# board.net
KiCad netlist of a schematic drawn in EAGLE
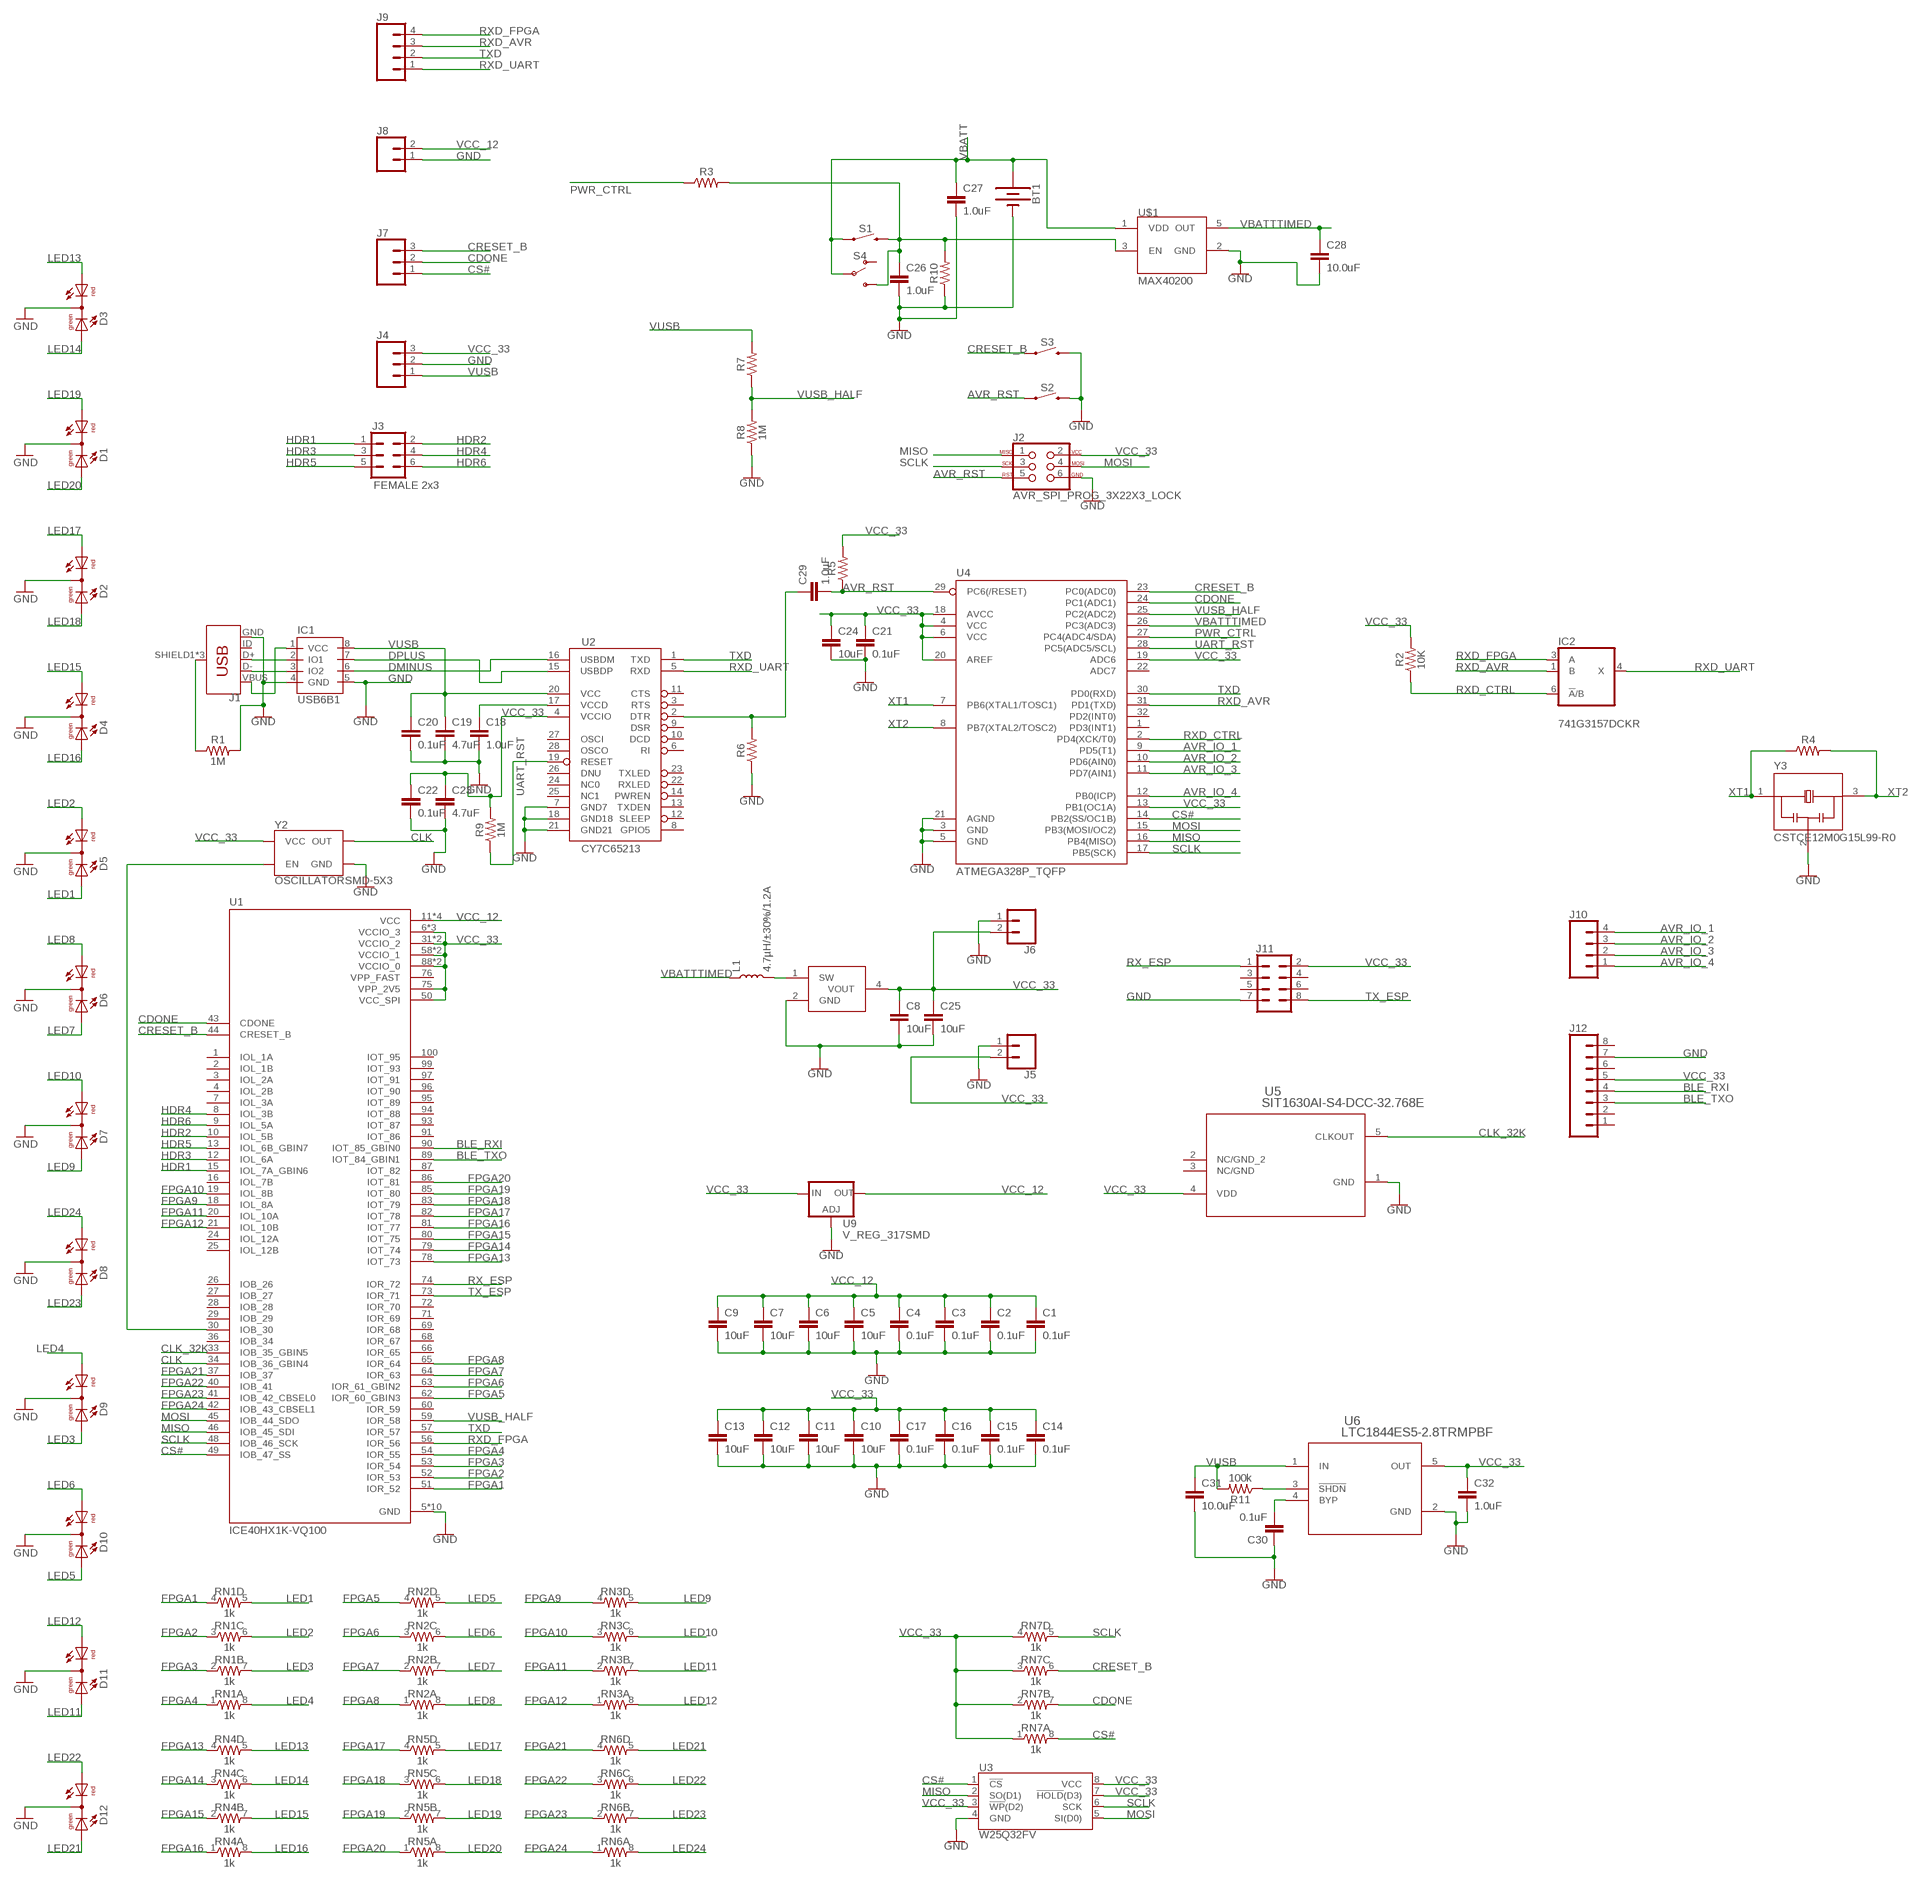
[diagram p0: schematic, sheet 1]

(export (version "E")
  (design (tool "Eeschema 10.0.6"))
  (components
    (comp (ref "BT1")
      (value "BATTERY-20MM_SMD")
      (footprint "eagle-import:BATTCON_20MM")
      (libsource (lib "eagle-import") (part "BATTERY-20MM_SMD"))
    )
    (comp (ref "C1")
      (value "0.1uF")
      (footprint "eagle-import:0805")
      (libsource (lib "eagle-import") (part "1.0UF-0805-25V-10%"))
    )
    (comp (ref "C2")
      (value "0.1uF")
      (footprint "eagle-import:0805")
      (libsource (lib "eagle-import") (part "1.0UF-0805-25V-10%"))
    )
    (comp (ref "C3")
      (value "0.1uF")
      (footprint "eagle-import:0805")
      (libsource (lib "eagle-import") (part "1.0UF-0805-25V-10%"))
    )
    (comp (ref "C4")
      (value "0.1uF")
      (footprint "eagle-import:0805")
      (libsource (lib "eagle-import") (part "1.0UF-0805-25V-10%"))
    )
    (comp (ref "C5")
      (value "10uF")
      (footprint "eagle-import:0805")
      (libsource (lib "eagle-import") (part "10UF-0805-10V-10%"))
    )
    (comp (ref "C6")
      (value "10uF")
      (footprint "eagle-import:0805")
      (libsource (lib "eagle-import") (part "10UF-0805-10V-10%"))
    )
    (comp (ref "C7")
      (value "10uF")
      (footprint "eagle-import:0805")
      (libsource (lib "eagle-import") (part "10UF-0805-10V-10%"))
    )
    (comp (ref "C8")
      (value "10uF")
      (footprint "eagle-import:0805")
      (libsource (lib "eagle-import") (part "22UF-0805-6.3V-20%"))
    )
    (comp (ref "C9")
      (value "10uF")
      (footprint "eagle-import:0805")
      (libsource (lib "eagle-import") (part "10UF-0805-10V-10%"))
    )
    (comp (ref "C10")
      (value "10uF")
      (footprint "eagle-import:0805")
      (libsource (lib "eagle-import") (part "10UF-0805-10V-10%"))
    )
    (comp (ref "C11")
      (value "10uF")
      (footprint "eagle-import:0805")
      (libsource (lib "eagle-import") (part "10UF-0805-10V-10%"))
    )
    (comp (ref "C12")
      (value "10uF")
      (footprint "eagle-import:0805")
      (libsource (lib "eagle-import") (part "10UF-0805-10V-10%"))
    )
    (comp (ref "C13")
      (value "10uF")
      (footprint "eagle-import:0805")
      (libsource (lib "eagle-import") (part "10UF-0805-10V-10%"))
    )
    (comp (ref "C14")
      (value "0.1uF")
      (footprint "eagle-import:0805")
      (libsource (lib "eagle-import") (part "1.0UF-0805-25V-(+80/-20%)"))
    )
    (comp (ref "C15")
      (value "0.1uF")
      (footprint "eagle-import:0805")
      (libsource (lib "eagle-import") (part "1.0UF-0805-25V-(+80/-20%)"))
    )
    (comp (ref "C16")
      (value "0.1uF")
      (footprint "eagle-import:0805")
      (libsource (lib "eagle-import") (part "1.0UF-0805-25V-(+80/-20%)"))
    )
    (comp (ref "C17")
      (value "0.1uF")
      (footprint "eagle-import:0805")
      (libsource (lib "eagle-import") (part "1.0UF-0805-25V-(+80/-20%)"))
    )
    (comp (ref "C18")
      (value "1.0uF")
      (footprint "eagle-import:0805")
      (libsource (lib "eagle-import") (part "1.0UF-0805-25V-10%"))
    )
    (comp (ref "C19")
      (value "4.7uF")
      (footprint "eagle-import:0805")
      (libsource (lib "eagle-import") (part "10UF-0805-10V-10%"))
    )
    (comp (ref "C20")
      (value "0.1uF")
      (footprint "eagle-import:0805")
      (libsource (lib "eagle-import") (part "1.0UF-0805-25V-10%"))
    )
    (comp (ref "C21")
      (value "0.1uF")
      (footprint "eagle-import:0805")
      (libsource (lib "eagle-import") (part "1.0UF-0805-25V-10%"))
    )
    (comp (ref "C22")
      (value "0.1uF")
      (footprint "eagle-import:0805")
      (libsource (lib "eagle-import") (part "1.0UF-0805-25V-10%"))
    )
    (comp (ref "C23")
      (value "4.7uF")
      (footprint "eagle-import:0805")
      (libsource (lib "eagle-import") (part "1.0UF-0805-25V-10%"))
    )
    (comp (ref "C24")
      (value "10uF")
      (footprint "eagle-import:0805")
      (libsource (lib "eagle-import") (part "1.0UF-0805-25V-10%"))
    )
    (comp (ref "C25")
      (value "10uF")
      (footprint "eagle-import:0805")
      (libsource (lib "eagle-import") (part "1.0UF-0805-25V-10%"))
    )
    (comp (ref "C26")
      (value "1.0uF")
      (footprint "eagle-import:0603")
      (libsource (lib "eagle-import") (part "1.0UF-0603-16V-10%"))
    )
    (comp (ref "C27")
      (value "1.0uF")
      (footprint "eagle-import:0603")
      (libsource (lib "eagle-import") (part "1.0UF-0603-16V-10%"))
    )
    (comp (ref "C28")
      (value "10.0uF")
      (footprint "eagle-import:0603")
      (libsource (lib "eagle-import") (part "1.0UF-0603-16V-10%"))
    )
    (comp (ref "C29")
      (value "1.0uF")
      (footprint "eagle-import:0805")
      (libsource (lib "eagle-import") (part "1.0UF-0805-25V-(+80/-20%)"))
    )
    (comp (ref "C30")
      (value "0.1uF")
      (footprint "eagle-import:0805")
      (libsource (lib "eagle-import") (part "1.0UF-0805-25V-(+80/-20%)"))
    )
    (comp (ref "C31")
      (value "10.0uF")
      (footprint "eagle-import:0805")
      (libsource (lib "eagle-import") (part "1.0UF-0805-25V-(+80/-20%)"))
    )
    (comp (ref "C32")
      (value "1.0uF")
      (footprint "eagle-import:0805")
      (libsource (lib "eagle-import") (part "1.0UF-0805-25V-(+80/-20%)"))
    )
    (comp (ref "D1")
      (value "DUOLED5MM")
      (footprint "eagle-import:DUOLED5MM")
      (libsource (lib "eagle-import") (part "DUOLED5MM"))
    )
    (comp (ref "D2")
      (value "DUOLED5MM")
      (footprint "eagle-import:DUOLED5MM")
      (libsource (lib "eagle-import") (part "DUOLED5MM"))
    )
    (comp (ref "D3")
      (value "DUOLED5MM")
      (footprint "eagle-import:DUOLED5MM")
      (libsource (lib "eagle-import") (part "DUOLED5MM"))
    )
    (comp (ref "D4")
      (value "DUOLED5MM")
      (footprint "eagle-import:DUOLED5MM")
      (libsource (lib "eagle-import") (part "DUOLED5MM"))
    )
    (comp (ref "D5")
      (value "DUOLED5MM")
      (footprint "eagle-import:DUOLED5MM")
      (libsource (lib "eagle-import") (part "DUOLED5MM"))
    )
    (comp (ref "D6")
      (value "DUOLED5MM")
      (footprint "eagle-import:DUOLED5MM")
      (libsource (lib "eagle-import") (part "DUOLED5MM"))
    )
    (comp (ref "D7")
      (value "DUOLED5MM")
      (footprint "eagle-import:DUOLED5MM")
      (libsource (lib "eagle-import") (part "DUOLED5MM"))
    )
    (comp (ref "D8")
      (value "DUOLED5MM")
      (footprint "eagle-import:DUOLED5MM")
      (libsource (lib "eagle-import") (part "DUOLED5MM"))
    )
    (comp (ref "D9")
      (value "DUOLED5MM")
      (footprint "eagle-import:DUOLED5MM")
      (libsource (lib "eagle-import") (part "DUOLED5MM"))
    )
    (comp (ref "D10")
      (value "DUOLED5MM")
      (footprint "eagle-import:DUOLED5MM")
      (libsource (lib "eagle-import") (part "DUOLED5MM"))
    )
    (comp (ref "D11")
      (value "DUOLED5MM")
      (footprint "eagle-import:DUOLED5MM")
      (libsource (lib "eagle-import") (part "DUOLED5MM"))
    )
    (comp (ref "D12")
      (value "DUOLED5MM")
      (footprint "eagle-import:DUOLED5MM")
      (libsource (lib "eagle-import") (part "DUOLED5MM"))
    )
    (comp (ref "IC1")
      (value "USB6B1")
      (footprint "eagle-import:SO08")
      (libsource (lib "eagle-import") (part "USB6B1"))
    )
    (comp (ref "IC2")
      (value "741G3157DCKR")
      (footprint "eagle-import:DCK_R-PDSO-G6")
      (libsource (lib "eagle-import") (part "741G3157DCKR"))
    )
    (comp (ref "J1")
      (value "USB_MICRO-B_FEMALE-SMT")
      (footprint "eagle-import:USB-B-MICRO-SMD")
      (libsource (lib "eagle-import") (part "USB_MICRO-B_FEMALE-SMT"))
    )
    (comp (ref "J2")
      (value "AVR_SPI_PROG_3X22X3_LOCK")
      (footprint "eagle-import:2X3_LOCK")
      (libsource (lib "eagle-import") (part "AVR_SPI_PROG_3X22X3_LOCK"))
    )
    (comp (ref "J3")
      (value "FEMALE 2x3")
      (footprint "eagle-import:2X3")
      (libsource (lib "eagle-import") (part "CONN_03X2FEMALE"))
    )
    (comp (ref "J4")
      (value "CONN_03LOCK")
      (footprint "eagle-import:1X03_LOCK")
      (libsource (lib "eagle-import") (part "CONN_03LOCK"))
    )
    (comp (ref "J5")
      (value "CONN_02LOCK")
      (footprint "eagle-import:1X02_LOCK")
      (libsource (lib "eagle-import") (part "CONN_02LOCK"))
    )
    (comp (ref "J6")
      (value "CONN_02LOCK")
      (footprint "eagle-import:1X02_LOCK")
      (libsource (lib "eagle-import") (part "CONN_02LOCK"))
    )
    (comp (ref "J7")
      (value "CONN_03LOCK")
      (footprint "eagle-import:1X03_LOCK")
      (libsource (lib "eagle-import") (part "CONN_03LOCK"))
    )
    (comp (ref "J8")
      (value "CONN_02LOCK")
      (footprint "eagle-import:1X02_LOCK")
      (libsource (lib "eagle-import") (part "CONN_02LOCK"))
    )
    (comp (ref "J9")
      (value "CONN_04LOCK")
      (footprint "eagle-import:1X04_LOCK")
      (libsource (lib "eagle-import") (part "CONN_04LOCK"))
    )
    (comp (ref "J10")
      (value "CONN_04LOCK")
      (footprint "eagle-import:1X04_LOCK")
      (libsource (lib "eagle-import") (part "CONN_04LOCK"))
    )
    (comp (ref "J11")
      (value "CONN_04X2")
      (footprint "eagle-import:2X4")
      (libsource (lib "eagle-import") (part "CONN_04X2"))
    )
    (comp (ref "J12")
      (value "CONN_08LOCK")
      (footprint "eagle-import:1X08_LOCK")
      (libsource (lib "eagle-import") (part "CONN_08LOCK"))
    )
    (comp (ref "L1")
      (value "4.7µH/±30%/1.2A")
      (footprint "eagle-import:INDUCTOR_4.7UH")
      (libsource (lib "eagle-import") (part "INDUCTOR-CDRH-4.7UH"))
    )
    (comp (ref "R1")
      (value "1M")
      (footprint "eagle-import:0805")
      (libsource (lib "eagle-import") (part "RESISTOR0805"))
    )
    (comp (ref "R2")
      (value "10K")
      (footprint "eagle-import:0805")
      (libsource (lib "eagle-import") (part "RESISTOR0805"))
    )
    (comp (ref "R3")
      (value "RESISTOR0805")
      (footprint "eagle-import:0805")
      (libsource (lib "eagle-import") (part "RESISTOR0805"))
    )
    (comp (ref "R4")
      (value "RESISTOR0805")
      (footprint "eagle-import:0805")
      (libsource (lib "eagle-import") (part "RESISTOR0805"))
    )
    (comp (ref "R5")
      (value "RESISTOR0805")
      (footprint "eagle-import:0805")
      (libsource (lib "eagle-import") (part "RESISTOR0805"))
    )
    (comp (ref "R6")
      (value "RESISTOR0805")
      (footprint "eagle-import:0805")
      (libsource (lib "eagle-import") (part "RESISTOR0805"))
    )
    (comp (ref "R7")
      (value "RESISTOR0805")
      (footprint "eagle-import:0805")
      (libsource (lib "eagle-import") (part "RESISTOR0805"))
    )
    (comp (ref "R8")
      (value "1M")
      (footprint "eagle-import:0805")
      (libsource (lib "eagle-import") (part "RESISTOR0805"))
    )
    (comp (ref "R9")
      (value "1M")
      (footprint "eagle-import:0805")
      (libsource (lib "eagle-import") (part "RESISTOR0805"))
    )
    (comp (ref "R10")
      (value "RESISTOR0805")
      (footprint "eagle-import:0805")
      (libsource (lib "eagle-import") (part "RESISTOR0805"))
    )
    (comp (ref "R11")
      (value "100k")
      (footprint "eagle-import:0805")
      (libsource (lib "eagle-import") (part "RESISTOR0805"))
    )
    (comp (ref "RN1")
      (value "1k")
      (footprint "eagle-import:0805-ARV")
      (libsource (lib "eagle-import") (part "1KOHM-ARRAY(4)-0805_ARV-1/10W-5%"))
    )
    (comp (ref "RN2")
      (value "1k")
      (footprint "eagle-import:0805-ARV")
      (libsource (lib "eagle-import") (part "1KOHM-ARRAY(4)-0805_ARV-1/10W-5%"))
    )
    (comp (ref "RN3")
      (value "1k")
      (footprint "eagle-import:0805-ARV")
      (libsource (lib "eagle-import") (part "1KOHM-ARRAY(4)-0805_ARV-1/10W-5%"))
    )
    (comp (ref "RN4")
      (value "1k")
      (footprint "eagle-import:0805-ARV")
      (libsource (lib "eagle-import") (part "1KOHM-ARRAY(4)-0805_ARV-1/10W-5%"))
    )
    (comp (ref "RN5")
      (value "1k")
      (footprint "eagle-import:0805-ARV")
      (libsource (lib "eagle-import") (part "1KOHM-ARRAY(4)-0805_ARV-1/10W-5%"))
    )
    (comp (ref "RN6")
      (value "1k")
      (footprint "eagle-import:0805-ARV")
      (libsource (lib "eagle-import") (part "1KOHM-ARRAY(4)-0805_ARV-1/10W-5%"))
    )
    (comp (ref "RN7")
      (value "1k")
      (footprint "eagle-import:0805-ARV")
      (libsource (lib "eagle-import") (part "1KOHM-ARRAY(4)-0805_ARV-1/10W-5%"))
    )
    (comp (ref "S1")
      (value "MOMENTARY-SWITCH-SPST-SMD-5.2MM")
      (footprint "eagle-import:TACTILE_SWITCH_SMD_5.2MM")
      (libsource (lib "eagle-import") (part "MOMENTARY-SWITCH-SPST-SMD-5.2MM"))
    )
    (comp (ref "S2")
      (value "MOMENTARY-SWITCH-SPST-SMD-5.2MM")
      (footprint "eagle-import:TACTILE_SWITCH_SMD_5.2MM")
      (libsource (lib "eagle-import") (part "MOMENTARY-SWITCH-SPST-SMD-5.2MM"))
    )
    (comp (ref "S3")
      (value "MOMENTARY-SWITCH-SPST-SMD-5.2MM")
      (footprint "eagle-import:TACTILE_SWITCH_SMD_5.2MM")
      (libsource (lib "eagle-import") (part "MOMENTARY-SWITCH-SPST-SMD-5.2MM"))
    )
    (comp (ref "S4")
      (value "SWITCH-SPDT-PTH-11.6X4.0MM")
      (footprint "eagle-import:SWITCH_SPDT_PTH_11.6X4.0MM")
      (libsource (lib "eagle-import") (part "SWITCH-SPDT-PTH-11.6X4.0MM"))
    )
    (comp (ref "U$1")
      (value "MAX40200")
      (footprint "eagle-import:SOT95P280X145-5N")
      (libsource (lib "eagle-import") (part "MAX40200"))
    )
    (comp (ref "U$2")
      (value "TPS613221A")
      (footprint "eagle-import:SOT95P280X145-5N")
      (libsource (lib "eagle-import") (part "TPS613221A"))
    )
    (comp (ref "U1")
      (value "ICE40HX1K-VQ100")
      (footprint "eagle-import:QFP50P1600X1600X120-100N")
      (fields (field (name "MF") "Lattice Semiconductor"))
      (libsource (lib "eagle-import") (part "ICE40HX1K-VQ100"))
    )
    (comp (ref "U2")
      (value "CY7C65213")
      (footprint "eagle-import:SSOP28DB")
      (libsource (lib "eagle-import") (part "CY7C65213"))
    )
    (comp (ref "U3")
      (value "W25Q32FV")
      (footprint "eagle-import:SOIC-8")
      (libsource (lib "eagle-import") (part "W25Q32FVSS"))
    )
    (comp (ref "U4")
      (value "ATMEGA328P_TQFP")
      (footprint "eagle-import:TQFP32-08")
      (libsource (lib "eagle-import") (part "ATMEGA328P_TQFP"))
    )
    (comp (ref "U5")
      (value "SIT1630AI-S4-DCC-32.768E")
      (footprint "eagle-import:SOT_SIT1630-S_SIT")
      (fields (field (name "COPYRIGHT") "Copyright (C) 2018 Accelerated Designs. All rights reserved"))
      (libsource (lib "eagle-import") (part "SIT1630AI-S4-DCC-32.768E"))
    )
    (comp (ref "U6")
      (value "LTC1844ES5-2.8TRMPBF")
      (footprint "eagle-import:S_5_ADI")
      (fields
        (field (name "MANUFACTURER_PART_NUMBER") "LTC1844ES5-2.8#TRMPBF")
        (field (name "COPYRIGHT") "Copyright (C) 2016 Accelerated Designs. All rights reserved")
      )
      (libsource (lib "eagle-import") (part "LTC1844ES5-2.8TRMPBF"))
    )
    (comp (ref "U9")
      (value "V_REG_317SMD")
      (footprint "eagle-import:SOT223")
      (libsource (lib "eagle-import") (part "V_REG_317SMD"))
    )
    (comp (ref "Y2")
      (value "OSCILLATORSMD-5X3")
      (footprint "eagle-import:OSCILLATOR-SMD-5X3.2")
      (libsource (lib "eagle-import") (part "OSCILLATORSMD-5X3"))
    )
    (comp (ref "Y3")
      (value "CSTCE12M0G15L99-R0")
      (footprint "eagle-import:OSC_CSTCE12M0G15L99-R0")
      (fields (field (name "MF") "Murata Electronics"))
      (libsource (lib "eagle-import") (part "CSTCE12M0G15L99-R0"))
    )
  )
  (nets
    (net (code "1") (name "/AVR_IO_1") (class "Default")
      (node (ref "J10") (pin "4") (pinfunction "4_4") (pintype "passive"))
      (node (ref "U4") (pin "9") (pinfunction "PD5(T1)_9") (pintype "bidirectional"))
    )
    (net (code "2") (name "/AVR_IO_2") (class "Default")
      (node (ref "J10") (pin "3") (pinfunction "3_3") (pintype "passive"))
      (node (ref "U4") (pin "10") (pinfunction "PD6(AIN0)_10") (pintype "bidirectional"))
    )
    (net (code "3") (name "/AVR_IO_3") (class "Default")
      (node (ref "J10") (pin "2") (pinfunction "2_2") (pintype "passive"))
      (node (ref "U4") (pin "11") (pinfunction "PD7(AIN1)_11") (pintype "bidirectional"))
    )
    (net (code "4") (name "/AVR_IO_4") (class "Default")
      (node (ref "J10") (pin "1") (pinfunction "1_1") (pintype "passive"))
      (node (ref "U4") (pin "12") (pinfunction "PB0(ICP)_12") (pintype "bidirectional"))
    )
    (net (code "5") (name "/AVR_RST") (class "Default")
      (node (ref "C29") (pin "2") (pinfunction "2_2") (pintype "passive"))
      (node (ref "J2") (pin "5") (pinfunction "5_5") (pintype "passive"))
      (node (ref "R5") (pin "1") (pinfunction "1_1") (pintype "passive"))
      (node (ref "S2") (pin "1") (pinfunction "1_1") (pintype "passive"))
      (node (ref "U4") (pin "29") (pinfunction "PC6(/RESET)_29") (pintype "bidirectional"))
    )
    (net (code "6") (name "/BLE_RXI") (class "Default")
      (node (ref "J12") (pin "4") (pinfunction "4_4") (pintype "passive"))
      (node (ref "U1") (pin "90") (pinfunction "IOT_85_GBIN0_90") (pintype "bidirectional"))
    )
    (net (code "7") (name "/BLE_TXO") (class "Default")
      (node (ref "J12") (pin "3") (pinfunction "3_3") (pintype "passive"))
      (node (ref "U1") (pin "89") (pinfunction "IOT_84_GBIN1_89") (pintype "bidirectional"))
    )
    (net (code "8") (name "/CDONE") (class "Default")
      (node (ref "J7") (pin "2") (pinfunction "2_2") (pintype "passive"))
      (node (ref "RN7") (pin "7") (pinfunction "2_7") (pintype "passive"))
      (node (ref "U1") (pin "43") (pinfunction "CDONE_43") (pintype "input"))
      (node (ref "U4") (pin "24") (pinfunction "PC1(ADC1)_24") (pintype "bidirectional"))
    )
    (net (code "9") (name "/CLK") (class "Default")
      (node (ref "U1") (pin "34") (pinfunction "IOB_36_GBIN4_34") (pintype "bidirectional"))
      (node (ref "Y2") (pin "3") (pinfunction "OUT_3") (pintype "bidirectional"))
    )
    (net (code "10") (name "/CLK_32K") (class "Default")
      (node (ref "U1") (pin "33") (pinfunction "IOB_35_GBIN5_33") (pintype "bidirectional"))
      (node (ref "U5") (pin "5") (pinfunction "CLKOUT_5") (pintype "output"))
    )
    (net (code "11") (name "/CRESET_B") (class "Default")
      (node (ref "J7") (pin "3") (pinfunction "3_3") (pintype "passive"))
      (node (ref "RN7") (pin "6") (pinfunction "2_6") (pintype "passive"))
      (node (ref "S3") (pin "1") (pinfunction "1_1") (pintype "passive"))
      (node (ref "U1") (pin "44") (pinfunction "CRESET_B_44") (pintype "input"))
      (node (ref "U4") (pin "23") (pinfunction "PC0(ADC0)_23") (pintype "bidirectional"))
    )
    (net (code "12") (name "/CS#") (class "Default")
      (node (ref "J7") (pin "1") (pinfunction "1_1") (pintype "passive"))
      (node (ref "RN7") (pin "8") (pinfunction "2_8") (pintype "passive"))
      (node (ref "U1") (pin "49") (pinfunction "IOB_47_SS_49") (pintype "bidirectional"))
      (node (ref "U3") (pin "1") (pinfunction "~{CS}_1") (pintype "bidirectional"))
      (node (ref "U4") (pin "14") (pinfunction "PB2(SS/OC1B)_14") (pintype "bidirectional"))
    )
    (net (code "13") (name "/DMINUS") (class "Default")
      (node (ref "IC1") (pin "6") (pinfunction "IO2_6") (pintype "bidirectional"))
      (node (ref "U2") (pin "16") (pinfunction "USBDM_16") (pintype "bidirectional"))
    )
    (net (code "14") (name "/DPLUS") (class "Default")
      (node (ref "IC1") (pin "7") (pinfunction "IO1_7") (pintype "bidirectional"))
      (node (ref "U2") (pin "15") (pinfunction "USBDP_15") (pintype "bidirectional"))
    )
    (net (code "15") (name "/FPGA1") (class "Default")
      (node (ref "RN1") (pin "4") (pinfunction "1_4") (pintype "passive"))
      (node (ref "U1") (pin "51") (pinfunction "IOR_52_51") (pintype "bidirectional"))
    )
    (net (code "16") (name "/FPGA2") (class "Default")
      (node (ref "RN1") (pin "3") (pinfunction "1_3") (pintype "passive"))
      (node (ref "U1") (pin "52") (pinfunction "IOR_53_52") (pintype "bidirectional"))
    )
    (net (code "17") (name "/FPGA3") (class "Default")
      (node (ref "RN1") (pin "2") (pinfunction "1_2") (pintype "passive"))
      (node (ref "U1") (pin "53") (pinfunction "IOR_54_53") (pintype "bidirectional"))
    )
    (net (code "18") (name "/FPGA4") (class "Default")
      (node (ref "RN1") (pin "1") (pinfunction "1_1") (pintype "passive"))
      (node (ref "U1") (pin "54") (pinfunction "IOR_55_54") (pintype "bidirectional"))
    )
    (net (code "19") (name "/FPGA5") (class "Default")
      (node (ref "RN2") (pin "4") (pinfunction "1_4") (pintype "passive"))
      (node (ref "U1") (pin "62") (pinfunction "IOR_60_GBIN3_62") (pintype "bidirectional"))
    )
    (net (code "20") (name "/FPGA6") (class "Default")
      (node (ref "RN2") (pin "3") (pinfunction "1_3") (pintype "passive"))
      (node (ref "U1") (pin "63") (pinfunction "IOR_61_GBIN2_63") (pintype "bidirectional"))
    )
    (net (code "21") (name "/FPGA7") (class "Default")
      (node (ref "RN2") (pin "2") (pinfunction "1_2") (pintype "passive"))
      (node (ref "U1") (pin "64") (pinfunction "IOR_63_64") (pintype "bidirectional"))
    )
    (net (code "22") (name "/FPGA8") (class "Default")
      (node (ref "RN2") (pin "1") (pinfunction "1_1") (pintype "passive"))
      (node (ref "U1") (pin "65") (pinfunction "IOR_64_65") (pintype "bidirectional"))
    )
    (net (code "23") (name "/FPGA9") (class "Default")
      (node (ref "RN3") (pin "4") (pinfunction "1_4") (pintype "passive"))
      (node (ref "U1") (pin "18") (pinfunction "IOL_8A_18") (pintype "bidirectional"))
    )
    (net (code "24") (name "/FPGA10") (class "Default")
      (node (ref "RN3") (pin "3") (pinfunction "1_3") (pintype "passive"))
      (node (ref "U1") (pin "19") (pinfunction "IOL_8B_19") (pintype "bidirectional"))
    )
    (net (code "25") (name "/FPGA11") (class "Default")
      (node (ref "RN3") (pin "2") (pinfunction "1_2") (pintype "passive"))
      (node (ref "U1") (pin "20") (pinfunction "IOL_10A_20") (pintype "bidirectional"))
    )
    (net (code "26") (name "/FPGA12") (class "Default")
      (node (ref "RN3") (pin "1") (pinfunction "1_1") (pintype "passive"))
      (node (ref "U1") (pin "21") (pinfunction "IOL_10B_21") (pintype "bidirectional"))
    )
    (net (code "27") (name "/FPGA13") (class "Default")
      (node (ref "RN4") (pin "4") (pinfunction "1_4") (pintype "passive"))
      (node (ref "U1") (pin "78") (pinfunction "IOT_73_78") (pintype "bidirectional"))
    )
    (net (code "28") (name "/FPGA14") (class "Default")
      (node (ref "RN4") (pin "3") (pinfunction "1_3") (pintype "passive"))
      (node (ref "U1") (pin "79") (pinfunction "IOT_74_79") (pintype "bidirectional"))
    )
    (net (code "29") (name "/FPGA15") (class "Default")
      (node (ref "RN4") (pin "2") (pinfunction "1_2") (pintype "passive"))
      (node (ref "U1") (pin "80") (pinfunction "IOT_75_80") (pintype "bidirectional"))
    )
    (net (code "30") (name "/FPGA16") (class "Default")
      (node (ref "RN4") (pin "1") (pinfunction "1_1") (pintype "passive"))
      (node (ref "U1") (pin "81") (pinfunction "IOT_77_81") (pintype "bidirectional"))
    )
    (net (code "31") (name "/FPGA17") (class "Default")
      (node (ref "RN5") (pin "4") (pinfunction "1_4") (pintype "passive"))
      (node (ref "U1") (pin "82") (pinfunction "IOT_78_82") (pintype "bidirectional"))
    )
    (net (code "32") (name "/FPGA18") (class "Default")
      (node (ref "RN5") (pin "3") (pinfunction "1_3") (pintype "passive"))
      (node (ref "U1") (pin "83") (pinfunction "IOT_79_83") (pintype "bidirectional"))
    )
    (net (code "33") (name "/FPGA19") (class "Default")
      (node (ref "RN5") (pin "2") (pinfunction "1_2") (pintype "passive"))
      (node (ref "U1") (pin "85") (pinfunction "IOT_80_85") (pintype "bidirectional"))
    )
    (net (code "34") (name "/FPGA20") (class "Default")
      (node (ref "RN5") (pin "1") (pinfunction "1_1") (pintype "passive"))
      (node (ref "U1") (pin "86") (pinfunction "IOT_81_86") (pintype "bidirectional"))
    )
    (net (code "35") (name "/FPGA21") (class "Default")
      (node (ref "RN6") (pin "4") (pinfunction "1_4") (pintype "passive"))
      (node (ref "U1") (pin "37") (pinfunction "IOB_37_37") (pintype "bidirectional"))
    )
    (net (code "36") (name "/FPGA22") (class "Default")
      (node (ref "RN6") (pin "3") (pinfunction "1_3") (pintype "passive"))
      (node (ref "U1") (pin "40") (pinfunction "IOB_41_40") (pintype "bidirectional"))
    )
    (net (code "37") (name "/FPGA23") (class "Default")
      (node (ref "RN6") (pin "2") (pinfunction "1_2") (pintype "passive"))
      (node (ref "U1") (pin "41") (pinfunction "IOB_42_CBSEL0_41") (pintype "bidirectional"))
    )
    (net (code "38") (name "/FPGA24") (class "Default")
      (node (ref "RN6") (pin "1") (pinfunction "1_1") (pintype "passive"))
      (node (ref "U1") (pin "42") (pinfunction "IOB_43_CBSEL1_42") (pintype "bidirectional"))
    )
    (net (code "39") (name "/HDR1") (class "Default")
      (node (ref "J3") (pin "1") (pinfunction "1_1") (pintype "bidirectional"))
      (node (ref "U1") (pin "15") (pinfunction "IOL_7A_GBIN6_15") (pintype "bidirectional"))
    )
    (net (code "40") (name "/HDR2") (class "Default")
      (node (ref "J3") (pin "2") (pinfunction "2_2") (pintype "bidirectional"))
      (node (ref "U1") (pin "10") (pinfunction "IOL_5B_10") (pintype "bidirectional"))
    )
    (net (code "41") (name "/HDR3") (class "Default")
      (node (ref "J3") (pin "3") (pinfunction "3_3") (pintype "bidirectional"))
      (node (ref "U1") (pin "12") (pinfunction "IOL_6A_12") (pintype "bidirectional"))
    )
    (net (code "42") (name "/HDR4") (class "Default")
      (node (ref "J3") (pin "4") (pinfunction "4_4") (pintype "bidirectional"))
      (node (ref "U1") (pin "8") (pinfunction "IOL_3B_8") (pintype "bidirectional"))
    )
    (net (code "43") (name "/HDR5") (class "Default")
      (node (ref "J3") (pin "5") (pinfunction "5_5") (pintype "bidirectional"))
      (node (ref "U1") (pin "13") (pinfunction "IOL_6B_GBIN7_13") (pintype "bidirectional"))
    )
    (net (code "44") (name "/HDR6") (class "Default")
      (node (ref "J3") (pin "6") (pinfunction "6_6") (pintype "bidirectional"))
      (node (ref "U1") (pin "9") (pinfunction "IOL_5A_9") (pintype "bidirectional"))
    )
    (net (code "45") (name "/LED1") (class "Default")
      (node (ref "D5") (pin "AG") (pinfunction "AG_AG") (pintype "passive"))
      (node (ref "RN1") (pin "5") (pinfunction "2_5") (pintype "passive"))
    )
    (net (code "46") (name "/LED2") (class "Default")
      (node (ref "D5") (pin "AR") (pinfunction "AR_AR") (pintype "passive"))
      (node (ref "RN1") (pin "6") (pinfunction "2_6") (pintype "passive"))
    )
    (net (code "47") (name "/LED3") (class "Default")
      (node (ref "D9") (pin "AG") (pinfunction "AG_AG") (pintype "passive"))
      (node (ref "RN1") (pin "7") (pinfunction "2_7") (pintype "passive"))
    )
    (net (code "48") (name "/LED4") (class "Default")
      (node (ref "D9") (pin "AR") (pinfunction "AR_AR") (pintype "passive"))
      (node (ref "RN1") (pin "8") (pinfunction "2_8") (pintype "passive"))
    )
    (net (code "49") (name "/LED5") (class "Default")
      (node (ref "D10") (pin "AG") (pinfunction "AG_AG") (pintype "passive"))
      (node (ref "RN2") (pin "5") (pinfunction "2_5") (pintype "passive"))
    )
    (net (code "50") (name "/LED6") (class "Default")
      (node (ref "D10") (pin "AR") (pinfunction "AR_AR") (pintype "passive"))
      (node (ref "RN2") (pin "6") (pinfunction "2_6") (pintype "passive"))
    )
    (net (code "51") (name "/LED7") (class "Default")
      (node (ref "D6") (pin "AG") (pinfunction "AG_AG") (pintype "passive"))
      (node (ref "RN2") (pin "7") (pinfunction "2_7") (pintype "passive"))
    )
    (net (code "52") (name "/LED8") (class "Default")
      (node (ref "D6") (pin "AR") (pinfunction "AR_AR") (pintype "passive"))
      (node (ref "RN2") (pin "8") (pinfunction "2_8") (pintype "passive"))
    )
    (net (code "53") (name "/LED9") (class "Default")
      (node (ref "D7") (pin "AG") (pinfunction "AG_AG") (pintype "passive"))
      (node (ref "RN3") (pin "5") (pinfunction "2_5") (pintype "passive"))
    )
    (net (code "54") (name "/LED10") (class "Default")
      (node (ref "D7") (pin "AR") (pinfunction "AR_AR") (pintype "passive"))
      (node (ref "RN3") (pin "6") (pinfunction "2_6") (pintype "passive"))
    )
    (net (code "55") (name "/LED11") (class "Default")
      (node (ref "D11") (pin "AG") (pinfunction "AG_AG") (pintype "passive"))
      (node (ref "RN3") (pin "7") (pinfunction "2_7") (pintype "passive"))
    )
    (net (code "56") (name "/LED12") (class "Default")
      (node (ref "D11") (pin "AR") (pinfunction "AR_AR") (pintype "passive"))
      (node (ref "RN3") (pin "8") (pinfunction "2_8") (pintype "passive"))
    )
    (net (code "57") (name "/LED13") (class "Default")
      (node (ref "D3") (pin "AR") (pinfunction "AR_AR") (pintype "passive"))
      (node (ref "RN4") (pin "5") (pinfunction "2_5") (pintype "passive"))
    )
    (net (code "58") (name "/LED14") (class "Default")
      (node (ref "D3") (pin "AG") (pinfunction "AG_AG") (pintype "passive"))
      (node (ref "RN4") (pin "6") (pinfunction "2_6") (pintype "passive"))
    )
    (net (code "59") (name "/LED15") (class "Default")
      (node (ref "D4") (pin "AR") (pinfunction "AR_AR") (pintype "passive"))
      (node (ref "RN4") (pin "7") (pinfunction "2_7") (pintype "passive"))
    )
    (net (code "60") (name "/LED16") (class "Default")
      (node (ref "D4") (pin "AG") (pinfunction "AG_AG") (pintype "passive"))
      (node (ref "RN4") (pin "8") (pinfunction "2_8") (pintype "passive"))
    )
    (net (code "61") (name "/LED17") (class "Default")
      (node (ref "D2") (pin "AR") (pinfunction "AR_AR") (pintype "passive"))
      (node (ref "RN5") (pin "5") (pinfunction "2_5") (pintype "passive"))
    )
    (net (code "62") (name "/LED18") (class "Default")
      (node (ref "D2") (pin "AG") (pinfunction "AG_AG") (pintype "passive"))
      (node (ref "RN5") (pin "6") (pinfunction "2_6") (pintype "passive"))
    )
    (net (code "63") (name "/LED19") (class "Default")
      (node (ref "D1") (pin "AR") (pinfunction "AR_AR") (pintype "passive"))
      (node (ref "RN5") (pin "7") (pinfunction "2_7") (pintype "passive"))
    )
    (net (code "64") (name "/LED20") (class "Default")
      (node (ref "D1") (pin "AG") (pinfunction "AG_AG") (pintype "passive"))
      (node (ref "RN5") (pin "8") (pinfunction "2_8") (pintype "passive"))
    )
    (net (code "65") (name "/LED21") (class "Default")
      (node (ref "D12") (pin "AG") (pinfunction "AG_AG") (pintype "passive"))
      (node (ref "RN6") (pin "5") (pinfunction "2_5") (pintype "passive"))
    )
    (net (code "66") (name "/LED22") (class "Default")
      (node (ref "D12") (pin "AR") (pinfunction "AR_AR") (pintype "passive"))
      (node (ref "RN6") (pin "6") (pinfunction "2_6") (pintype "passive"))
    )
    (net (code "67") (name "/LED23") (class "Default")
      (node (ref "D8") (pin "AG") (pinfunction "AG_AG") (pintype "passive"))
      (node (ref "RN6") (pin "7") (pinfunction "2_7") (pintype "passive"))
    )
    (net (code "68") (name "/LED24") (class "Default")
      (node (ref "D8") (pin "AR") (pinfunction "AR_AR") (pintype "passive"))
      (node (ref "RN6") (pin "8") (pinfunction "2_8") (pintype "passive"))
    )
    (net (code "69") (name "/MISO") (class "Default")
      (node (ref "J2") (pin "1") (pinfunction "1_1") (pintype "passive"))
      (node (ref "U1") (pin "46") (pinfunction "IOB_45_SDI_46") (pintype "bidirectional"))
      (node (ref "U3") (pin "2") (pinfunction "SO(D1)_2") (pintype "bidirectional"))
      (node (ref "U4") (pin "16") (pinfunction "PB4(MISO)_16") (pintype "bidirectional"))
    )
    (net (code "70") (name "/MOSI") (class "Default")
      (node (ref "J2") (pin "4") (pinfunction "4_4") (pintype "passive"))
      (node (ref "U1") (pin "45") (pinfunction "IOB_44_SDO_45") (pintype "bidirectional"))
      (node (ref "U3") (pin "5") (pinfunction "SI(D0)_5") (pintype "bidirectional"))
      (node (ref "U4") (pin "15") (pinfunction "PB3(MOSI/OC2)_15") (pintype "bidirectional"))
    )
    (net (code "71") (name "/NC1") (class "Default")
      (node (ref "U2") (pin "25") (pinfunction "NC1_25") (pintype "power_in"))
    )
    (net (code "72") (name "/PWR_CTRL") (class "Default")
      (node (ref "R3") (pin "1") (pinfunction "1_1") (pintype "passive"))
      (node (ref "U4") (pin "27") (pinfunction "PC4(ADC4/SDA)_27") (pintype "bidirectional"))
    )
    (net (code "73") (name "/RXD_AVR") (class "Default")
      (node (ref "IC2") (pin "1") (pinfunction "B_1") (pintype "bidirectional"))
      (node (ref "J9") (pin "3") (pinfunction "3_3") (pintype "passive"))
      (node (ref "U4") (pin "31") (pinfunction "PD1(TXD)_31") (pintype "bidirectional"))
    )
    (net (code "74") (name "/RXD_CTRL") (class "Default")
      (node (ref "IC2") (pin "6") (pinfunction "~{A}/B_6") (pintype "input"))
      (node (ref "R2") (pin "1") (pinfunction "1_1") (pintype "passive"))
      (node (ref "U4") (pin "2") (pinfunction "PD4(XCK/T0)_2") (pintype "bidirectional"))
    )
    (net (code "75") (name "/RXD_FPGA") (class "Default")
      (node (ref "IC2") (pin "3") (pinfunction "A_3") (pintype "bidirectional"))
      (node (ref "J9") (pin "4") (pinfunction "4_4") (pintype "passive"))
      (node (ref "U1") (pin "56") (pinfunction "IOR_56_56") (pintype "bidirectional"))
    )
    (net (code "76") (name "/RXD_UART") (class "Default")
      (node (ref "IC2") (pin "4") (pinfunction "X_4") (pintype "bidirectional"))
      (node (ref "J9") (pin "1") (pinfunction "1_1") (pintype "passive"))
      (node (ref "U2") (pin "5") (pinfunction "RXD_5") (pintype "input"))
    )
    (net (code "77") (name "/RX_ESP") (class "Default")
      (node (ref "J11") (pin "1") (pinfunction "1_1") (pintype "passive"))
      (node (ref "U1") (pin "74") (pinfunction "IOR_72_74") (pintype "bidirectional"))
    )
    (net (code "78") (name "/SCLK") (class "Default")
      (node (ref "J2") (pin "3") (pinfunction "3_3") (pintype "passive"))
      (node (ref "RN7") (pin "5") (pinfunction "2_5") (pintype "passive"))
      (node (ref "U1") (pin "48") (pinfunction "IOB_46_SCK_48") (pintype "bidirectional"))
      (node (ref "U3") (pin "6") (pinfunction "SCK_6") (pintype "bidirectional"))
      (node (ref "U4") (pin "17") (pinfunction "PB5(SCK)_17") (pintype "bidirectional"))
    )
    (net (code "79") (name "/TXD") (class "Default")
      (node (ref "J9") (pin "2") (pinfunction "2_2") (pintype "passive"))
      (node (ref "U1") (pin "57") (pinfunction "IOR_57_57") (pintype "bidirectional"))
      (node (ref "U2") (pin "1") (pinfunction "TXD_1") (pintype "output"))
      (node (ref "U4") (pin "30") (pinfunction "PD0(RXD)_30") (pintype "bidirectional"))
    )
    (net (code "80") (name "/TX_ESP") (class "Default")
      (node (ref "J11") (pin "8") (pinfunction "8_8") (pintype "passive"))
      (node (ref "U1") (pin "73") (pinfunction "IOR_71_73") (pintype "bidirectional"))
    )
    (net (code "81") (name "/UART_RST") (class "Default")
      (node (ref "R9") (pin "1") (pinfunction "1_1") (pintype "passive"))
      (node (ref "U2") (pin "19") (pinfunction "RESET_19") (pintype "input"))
      (node (ref "U4") (pin "28") (pinfunction "PC5(ADC5/SCL)_28") (pintype "bidirectional"))
    )
    (net (code "82") (name "/VBATT") (class "Default")
      (node (ref "BT1") (pin "1") (pinfunction "+_1") (pintype "power_in"))
      (node (ref "C27") (pin "1") (pinfunction "1_1") (pintype "passive"))
      (node (ref "S1") (pin "1") (pinfunction "1_1") (pintype "passive"))
      (node (ref "S4") (pin "2") (pinfunction "P_2") (pintype "passive"))
      (node (ref "U$1") (pin "1") (pinfunction "VDD_1") (pintype "bidirectional"))
    )
    (net (code "83") (name "/VBATTTIMED") (class "Default")
      (node (ref "C28") (pin "1") (pinfunction "1_1") (pintype "passive"))
      (node (ref "L1") (pin "P$1") (pinfunction "1_P$1") (pintype "passive"))
      (node (ref "U$1") (pin "5") (pinfunction "OUT_5") (pintype "bidirectional"))
      (node (ref "U4") (pin "26") (pinfunction "PC3(ADC3)_26") (pintype "bidirectional"))
    )
    (net (code "84") (name "/VCC_12") (class "Default")
      (node (ref "C1") (pin "1") (pinfunction "1_1") (pintype "passive"))
      (node (ref "C2") (pin "1") (pinfunction "1_1") (pintype "passive"))
      (node (ref "C3") (pin "1") (pinfunction "1_1") (pintype "passive"))
      (node (ref "C4") (pin "1") (pinfunction "1_1") (pintype "passive"))
      (node (ref "C5") (pin "1") (pinfunction "1_1") (pintype "passive"))
      (node (ref "C6") (pin "1") (pinfunction "1_1") (pintype "passive"))
      (node (ref "C7") (pin "1") (pinfunction "1_1") (pintype "passive"))
      (node (ref "C9") (pin "1") (pinfunction "1_1") (pintype "passive"))
      (node (ref "J8") (pin "2") (pinfunction "2_2") (pintype "passive"))
      (node (ref "U1") (pin "11") (pinfunction "VCC_11") (pintype "power_in"))
      (node (ref "U1") (pin "35") (pinfunction "VCC_35") (pintype "power_in"))
      (node (ref "U1") (pin "61") (pinfunction "VCC_61") (pintype "power_in"))
      (node (ref "U1") (pin "77") (pinfunction "VCC_77") (pintype "power_in"))
      (node (ref "U9") (pin "2") (pinfunction "OUT_2") (pintype "output"))
    )
    (net (code "85") (name "/VCC_33") (class "Default")
      (node (ref "C10") (pin "1") (pinfunction "1_1") (pintype "passive"))
      (node (ref "C11") (pin "1") (pinfunction "1_1") (pintype "passive"))
      (node (ref "C12") (pin "1") (pinfunction "1_1") (pintype "passive"))
      (node (ref "C13") (pin "1") (pinfunction "1_1") (pintype "passive"))
      (node (ref "C14") (pin "1") (pinfunction "1_1") (pintype "passive"))
      (node (ref "C15") (pin "1") (pinfunction "1_1") (pintype "passive"))
      (node (ref "C16") (pin "1") (pinfunction "1_1") (pintype "passive"))
      (node (ref "C17") (pin "1") (pinfunction "1_1") (pintype "passive"))
      (node (ref "C21") (pin "1") (pinfunction "1_1") (pintype "passive"))
      (node (ref "C22") (pin "1") (pinfunction "1_1") (pintype "passive"))
      (node (ref "C23") (pin "1") (pinfunction "1_1") (pintype "passive"))
      (node (ref "C24") (pin "1") (pinfunction "1_1") (pintype "passive"))
      (node (ref "C25") (pin "1") (pinfunction "1_1") (pintype "passive"))
      (node (ref "C32") (pin "1") (pinfunction "1_1") (pintype "passive"))
      (node (ref "C8") (pin "1") (pinfunction "1_1") (pintype "passive"))
      (node (ref "J11") (pin "2") (pinfunction "2_2") (pintype "passive"))
      (node (ref "J12") (pin "5") (pinfunction "5_5") (pintype "passive"))
      (node (ref "J2") (pin "2") (pinfunction "2_2") (pintype "passive"))
      (node (ref "J4") (pin "3") (pinfunction "3_3") (pintype "passive"))
      (node (ref "J5") (pin "2") (pinfunction "2_2") (pintype "passive"))
      (node (ref "J6") (pin "2") (pinfunction "2_2") (pintype "passive"))
      (node (ref "R2") (pin "2") (pinfunction "2_2") (pintype "passive"))
      (node (ref "R5") (pin "2") (pinfunction "2_2") (pintype "passive"))
      (node (ref "R9") (pin "2") (pinfunction "2_2") (pintype "passive"))
      (node (ref "RN7") (pin "1") (pinfunction "1_1") (pintype "passive"))
      (node (ref "RN7") (pin "2") (pinfunction "1_2") (pintype "passive"))
      (node (ref "RN7") (pin "3") (pinfunction "1_3") (pintype "passive"))
      (node (ref "RN7") (pin "4") (pinfunction "1_4") (pintype "passive"))
      (node (ref "U$2") (pin "4") (pinfunction "VOUT_4") (pintype "bidirectional"))
      (node (ref "U1") (pin "14") (pinfunction "VCCIO_3_14") (pintype "power_in"))
      (node (ref "U1") (pin "22") (pinfunction "VCCIO_3_22") (pintype "power_in"))
      (node (ref "U1") (pin "31") (pinfunction "VCCIO_2_31") (pintype "power_in"))
      (node (ref "U1") (pin "38") (pinfunction "VCCIO_2_38") (pintype "power_in"))
      (node (ref "U1") (pin "50") (pinfunction "VCC_SPI_50") (pintype "power_in"))
      (node (ref "U1") (pin "58") (pinfunction "VCCIO_1_58") (pintype "power_in"))
      (node (ref "U1") (pin "6") (pinfunction "VCCIO_3_6") (pintype "power_in"))
      (node (ref "U1") (pin "67") (pinfunction "VCCIO_1_67") (pintype "power_in"))
      (node (ref "U1") (pin "75") (pinfunction "VPP_2V5_75") (pintype "power_in"))
      (node (ref "U1") (pin "88") (pinfunction "VCCIO_0_88") (pintype "power_in"))
      (node (ref "U1") (pin "92") (pinfunction "VCCIO_0_92") (pintype "power_in"))
      (node (ref "U2") (pin "4") (pinfunction "VCCIO_4") (pintype "power_in"))
      (node (ref "U3") (pin "3") (pinfunction "~{WP}(D2)_3") (pintype "bidirectional"))
      (node (ref "U3") (pin "7") (pinfunction "~{HOLD}(D3)_7") (pintype "bidirectional"))
      (node (ref "U3") (pin "8") (pinfunction "VCC_8") (pintype "bidirectional"))
      (node (ref "U4") (pin "13") (pinfunction "PB1(OC1A)_13") (pintype "bidirectional"))
      (node (ref "U4") (pin "18") (pinfunction "AVCC_18") (pintype "bidirectional"))
      (node (ref "U4") (pin "19") (pinfunction "ADC6_19") (pintype "bidirectional"))
      (node (ref "U4") (pin "20") (pinfunction "AREF_20") (pintype "bidirectional"))
      (node (ref "U4") (pin "4") (pinfunction "VCC_4") (pintype "bidirectional"))
      (node (ref "U4") (pin "6") (pinfunction "VCC_6") (pintype "bidirectional"))
      (node (ref "U5") (pin "4") (pinfunction "VDD_4") (pintype "power_in"))
      (node (ref "U6") (pin "5") (pinfunction "OUT_5") (pintype "output"))
      (node (ref "U9") (pin "3") (pinfunction "IN_3") (pintype "input"))
      (node (ref "Y2") (pin "4") (pinfunction "VCC_4") (pintype "bidirectional"))
    )
    (net (code "86") (name "/VPP_FAST") (class "Default")
      (node (ref "U1") (pin "76") (pinfunction "VPP_FAST_76") (pintype "power_in"))
    )
    (net (code "87") (name "/VUSB") (class "Default")
      (node (ref "C19") (pin "1") (pinfunction "1_1") (pintype "passive"))
      (node (ref "C20") (pin "1") (pinfunction "1_1") (pintype "passive"))
      (node (ref "C31") (pin "1") (pinfunction "1_1") (pintype "passive"))
      (node (ref "IC1") (pin "8") (pinfunction "VCC_8") (pintype "power_in"))
      (node (ref "J4") (pin "1") (pinfunction "1_1") (pintype "passive"))
      (node (ref "R11") (pin "2") (pinfunction "2_2") (pintype "passive"))
      (node (ref "R7") (pin "2") (pinfunction "2_2") (pintype "passive"))
      (node (ref "U2") (pin "20") (pinfunction "VCC_20") (pintype "power_in"))
      (node (ref "U6") (pin "1") (pinfunction "IN_1") (pintype "input"))
    )
    (net (code "88") (name "/VUSB_HALF") (class "Default")
      (node (ref "R7") (pin "1") (pinfunction "1_1") (pintype "passive"))
      (node (ref "R8") (pin "2") (pinfunction "2_2") (pintype "passive"))
      (node (ref "U1") (pin "59") (pinfunction "IOR_58_59") (pintype "bidirectional"))
      (node (ref "U4") (pin "25") (pinfunction "PC2(ADC2)_25") (pintype "bidirectional"))
    )
    (net (code "89") (name "/XT1") (class "Default")
      (node (ref "R4") (pin "1") (pinfunction "1_1") (pintype "passive"))
      (node (ref "U4") (pin "7") (pinfunction "PB6(XTAL1/TOSC1)_7") (pintype "bidirectional"))
      (node (ref "Y3") (pin "1") (pinfunction "1_1") (pintype "passive"))
    )
    (net (code "90") (name "/XT2") (class "Default")
      (node (ref "R4") (pin "2") (pinfunction "2_2") (pintype "passive"))
      (node (ref "U4") (pin "8") (pinfunction "PB7(XTAL2/TOSC2)_8") (pintype "bidirectional"))
      (node (ref "Y3") (pin "3") (pinfunction "3_3") (pintype "passive"))
    )
    (net (code "91") (name "GND") (class "Default")
      (node (ref "BT1") (pin "2") (pinfunction "-_2") (pintype "power_in"))
      (node (ref "C1") (pin "2") (pinfunction "2_2") (pintype "passive"))
      (node (ref "C10") (pin "2") (pinfunction "2_2") (pintype "passive"))
      (node (ref "C11") (pin "2") (pinfunction "2_2") (pintype "passive"))
      (node (ref "C12") (pin "2") (pinfunction "2_2") (pintype "passive"))
      (node (ref "C13") (pin "2") (pinfunction "2_2") (pintype "passive"))
      (node (ref "C14") (pin "2") (pinfunction "2_2") (pintype "passive"))
      (node (ref "C15") (pin "2") (pinfunction "2_2") (pintype "passive"))
      (node (ref "C16") (pin "2") (pinfunction "2_2") (pintype "passive"))
      (node (ref "C17") (pin "2") (pinfunction "2_2") (pintype "passive"))
      (node (ref "C18") (pin "2") (pinfunction "2_2") (pintype "passive"))
      (node (ref "C19") (pin "2") (pinfunction "2_2") (pintype "passive"))
      (node (ref "C2") (pin "2") (pinfunction "2_2") (pintype "passive"))
      (node (ref "C20") (pin "2") (pinfunction "2_2") (pintype "passive"))
      (node (ref "C21") (pin "2") (pinfunction "2_2") (pintype "passive"))
      (node (ref "C22") (pin "2") (pinfunction "2_2") (pintype "passive"))
      (node (ref "C23") (pin "2") (pinfunction "2_2") (pintype "passive"))
      (node (ref "C24") (pin "2") (pinfunction "2_2") (pintype "passive"))
      (node (ref "C25") (pin "2") (pinfunction "2_2") (pintype "passive"))
      (node (ref "C26") (pin "2") (pinfunction "2_2") (pintype "passive"))
      (node (ref "C27") (pin "2") (pinfunction "2_2") (pintype "passive"))
      (node (ref "C28") (pin "2") (pinfunction "2_2") (pintype "passive"))
      (node (ref "C3") (pin "2") (pinfunction "2_2") (pintype "passive"))
      (node (ref "C30") (pin "1") (pinfunction "1_1") (pintype "passive"))
      (node (ref "C31") (pin "2") (pinfunction "2_2") (pintype "passive"))
      (node (ref "C32") (pin "2") (pinfunction "2_2") (pintype "passive"))
      (node (ref "C4") (pin "2") (pinfunction "2_2") (pintype "passive"))
      (node (ref "C5") (pin "2") (pinfunction "2_2") (pintype "passive"))
      (node (ref "C6") (pin "2") (pinfunction "2_2") (pintype "passive"))
      (node (ref "C7") (pin "2") (pinfunction "2_2") (pintype "passive"))
      (node (ref "C8") (pin "2") (pinfunction "2_2") (pintype "passive"))
      (node (ref "C9") (pin "2") (pinfunction "2_2") (pintype "passive"))
      (node (ref "D1") (pin "K") (pinfunction "C_K") (pintype "passive"))
      (node (ref "D10") (pin "K") (pinfunction "C_K") (pintype "passive"))
      (node (ref "D11") (pin "K") (pinfunction "C_K") (pintype "passive"))
      (node (ref "D12") (pin "K") (pinfunction "C_K") (pintype "passive"))
      (node (ref "D2") (pin "K") (pinfunction "C_K") (pintype "passive"))
      (node (ref "D3") (pin "K") (pinfunction "C_K") (pintype "passive"))
      (node (ref "D4") (pin "K") (pinfunction "C_K") (pintype "passive"))
      (node (ref "D5") (pin "K") (pinfunction "C_K") (pintype "passive"))
      (node (ref "D6") (pin "K") (pinfunction "C_K") (pintype "passive"))
      (node (ref "D7") (pin "K") (pinfunction "C_K") (pintype "passive"))
      (node (ref "D8") (pin "K") (pinfunction "C_K") (pintype "passive"))
      (node (ref "D9") (pin "K") (pinfunction "C_K") (pintype "passive"))
      (node (ref "IC1") (pin "4") (pinfunction "GND_4") (pintype "power_in"))
      (node (ref "IC1") (pin "5") (pinfunction "GND_5") (pintype "power_in"))
      (node (ref "J1") (pin "GND") (pinfunction "GND_GND") (pintype "power_in"))
      (node (ref "J11") (pin "7") (pinfunction "7_7") (pintype "passive"))
      (node (ref "J12") (pin "7") (pinfunction "7_7") (pintype "passive"))
      (node (ref "J2") (pin "6") (pinfunction "6_6") (pintype "passive"))
      (node (ref "J4") (pin "2") (pinfunction "2_2") (pintype "passive"))
      (node (ref "J5") (pin "1") (pinfunction "1_1") (pintype "passive"))
      (node (ref "J6") (pin "1") (pinfunction "1_1") (pintype "passive"))
      (node (ref "J8") (pin "1") (pinfunction "1_1") (pintype "passive"))
      (node (ref "R1") (pin "2") (pinfunction "2_2") (pintype "passive"))
      (node (ref "R10") (pin "1") (pinfunction "1_1") (pintype "passive"))
      (node (ref "R6") (pin "1") (pinfunction "1_1") (pintype "passive"))
      (node (ref "R8") (pin "1") (pinfunction "1_1") (pintype "passive"))
      (node (ref "S2") (pin "3") (pinfunction "2_3") (pintype "passive"))
      (node (ref "S3") (pin "3") (pinfunction "2_3") (pintype "passive"))
      (node (ref "U$1") (pin "2") (pinfunction "GND_2") (pintype "bidirectional"))
      (node (ref "U$2") (pin "2") (pinfunction "GND_2") (pintype "bidirectional"))
      (node (ref "U1") (pin "17") (pinfunction "GND_17") (pintype "power_in"))
      (node (ref "U1") (pin "23") (pinfunction "GND_23") (pintype "power_in"))
      (node (ref "U1") (pin "32") (pinfunction "GND_32") (pintype "power_in"))
      (node (ref "U1") (pin "39") (pinfunction "GND_39") (pintype "power_in"))
      (node (ref "U1") (pin "47") (pinfunction "GND_47") (pintype "power_in"))
      (node (ref "U1") (pin "5") (pinfunction "GND_5") (pintype "power_in"))
      (node (ref "U1") (pin "55") (pinfunction "GND_55") (pintype "power_in"))
      (node (ref "U1") (pin "70") (pinfunction "GND_70") (pintype "power_in"))
      (node (ref "U1") (pin "84") (pinfunction "GND_84") (pintype "power_in"))
      (node (ref "U1") (pin "98") (pinfunction "GND_98") (pintype "power_in"))
      (node (ref "U2") (pin "18") (pinfunction "GND18_18") (pintype "power_in"))
      (node (ref "U2") (pin "21") (pinfunction "GND21_21") (pintype "power_in"))
      (node (ref "U2") (pin "7") (pinfunction "GND7_7") (pintype "power_in"))
      (node (ref "U3") (pin "4") (pinfunction "GND_4") (pintype "bidirectional"))
      (node (ref "U4") (pin "21") (pinfunction "AGND_21") (pintype "bidirectional"))
      (node (ref "U4") (pin "3") (pinfunction "GND_3") (pintype "bidirectional"))
      (node (ref "U4") (pin "5") (pinfunction "GND_5") (pintype "bidirectional"))
      (node (ref "U5") (pin "1") (pinfunction "GND_1") (pintype "passive"))
      (node (ref "U6") (pin "2") (pinfunction "GND_2") (pintype "passive"))
      (node (ref "U9") (pin "1") (pinfunction "ADJ_1") (pintype "input"))
      (node (ref "Y2") (pin "2") (pinfunction "GND_2") (pintype "bidirectional"))
      (node (ref "Y3") (pin "2") (pinfunction "2_2") (pintype "power_in"))
    )
    (net (code "92") (name "Net-(IC1-IO1-Pad2)") (class "Default")
      (node (ref "IC1") (pin "2") (pinfunction "IO1_2") (pintype "bidirectional"))
      (node (ref "J1") (pin "D+") (pinfunction "D+_D+") (pintype "bidirectional"))
    )
    (net (code "93") (name "Net-(IC1-IO2-Pad3)") (class "Default")
      (node (ref "IC1") (pin "3") (pinfunction "IO2_3") (pintype "bidirectional"))
      (node (ref "J1") (pin "D-") (pinfunction "D-_D-") (pintype "bidirectional"))
    )
    (net (code "94") (name "Net-(IC1-VCC-Pad1)") (class "Default")
      (node (ref "IC1") (pin "1") (pinfunction "VCC_1") (pintype "power_in"))
      (node (ref "J1") (pin "VBUS") (pinfunction "VBUS_VBUS") (pintype "power_in"))
    )
    (net (code "95") (name "Net-(J1-SHIELD-PadSHIELD1)") (class "Default")
      (node (ref "J1") (pin "SHIELD1") (pinfunction "SHIELD_SHIELD1") (pintype "bidirectional"))
      (node (ref "J1") (pin "SHIELD2") (pinfunction "SHIELD_SHIELD2") (pintype "bidirectional"))
      (node (ref "J1") (pin "SHIELD3") (pinfunction "SHIELD_SHIELD3") (pintype "bidirectional"))
      (node (ref "R1") (pin "1") (pinfunction "1_1") (pintype "passive"))
    )
    (net (code "96") (name "Net-(L1-2)") (class "Default")
      (node (ref "L1") (pin "P$2") (pinfunction "2_P$2") (pintype "passive"))
      (node (ref "U$2") (pin "1") (pinfunction "SW_1") (pintype "bidirectional"))
    )
    (net (code "97") (name "Net-(S1-2)") (class "Default")
      (node (ref "C26") (pin "1") (pinfunction "1_1") (pintype "passive"))
      (node (ref "R10") (pin "2") (pinfunction "2_2") (pintype "passive"))
      (node (ref "R3") (pin "2") (pinfunction "2_2") (pintype "passive"))
      (node (ref "S1") (pin "3") (pinfunction "2_3") (pintype "passive"))
      (node (ref "S4") (pin "3") (pinfunction "S_3") (pintype "passive"))
      (node (ref "U$1") (pin "3") (pinfunction "EN_3") (pintype "bidirectional"))
    )
    (net (code "98") (name "Net-(U1-IOB_30)") (class "Default")
      (node (ref "U1") (pin "30") (pinfunction "IOB_30_30") (pintype "bidirectional"))
      (node (ref "Y2") (pin "1") (pinfunction "EN_1") (pintype "bidirectional"))
    )
    (net (code "99") (name "Net-(U2-DTR)") (class "Default")
      (node (ref "C29") (pin "1") (pinfunction "1_1") (pintype "passive"))
      (node (ref "R6") (pin "2") (pinfunction "2_2") (pintype "passive"))
      (node (ref "U2") (pin "2") (pinfunction "DTR_2") (pintype "output"))
    )
    (net (code "100") (name "Net-(U2-VCCD)") (class "Default")
      (node (ref "C18") (pin "1") (pinfunction "1_1") (pintype "passive"))
      (node (ref "U2") (pin "17") (pinfunction "VCCD_17") (pintype "output"))
    )
    (net (code "101") (name "Net-(U6-BYP)") (class "Default")
      (node (ref "C30") (pin "2") (pinfunction "2_2") (pintype "passive"))
      (node (ref "U6") (pin "4") (pinfunction "BYP_4") (pintype "passive"))
    )
    (net (code "102") (name "Net-(U6-~{SHDN})") (class "Default")
      (node (ref "R11") (pin "1") (pinfunction "1_1") (pintype "passive"))
      (node (ref "U6") (pin "3") (pinfunction "~{SHDN}_3") (pintype "passive"))
    )
    (net (code "103") (name "unconnected-(J1-PadID)") (class "Default")
      (node (ref "J1") (pin "ID") (pinfunction "ID_ID") (pintype "bidirectional"))
    )
    (net (code "104") (name "unconnected-(J11-Pad3)") (class "Default")
      (node (ref "J11") (pin "3") (pinfunction "3_3") (pintype "passive"))
    )
    (net (code "105") (name "unconnected-(J11-Pad4)") (class "Default")
      (node (ref "J11") (pin "4") (pinfunction "4_4") (pintype "passive"))
    )
    (net (code "106") (name "unconnected-(J11-Pad5)") (class "Default")
      (node (ref "J11") (pin "5") (pinfunction "5_5") (pintype "passive"))
    )
    (net (code "107") (name "unconnected-(J11-Pad6)") (class "Default")
      (node (ref "J11") (pin "6") (pinfunction "6_6") (pintype "passive"))
    )
    (net (code "108") (name "unconnected-(J12-Pad1)") (class "Default")
      (node (ref "J12") (pin "1") (pinfunction "1_1") (pintype "passive"))
    )
    (net (code "109") (name "unconnected-(J12-Pad2)") (class "Default")
      (node (ref "J12") (pin "2") (pinfunction "2_2") (pintype "passive"))
    )
    (net (code "110") (name "unconnected-(J12-Pad6)") (class "Default")
      (node (ref "J12") (pin "6") (pinfunction "6_6") (pintype "passive"))
    )
    (net (code "111") (name "unconnected-(J12-Pad8)") (class "Default")
      (node (ref "J12") (pin "8") (pinfunction "8_8") (pintype "passive"))
    )
    (net (code "112") (name "unconnected-(S4-O-Pad1)") (class "Default")
      (node (ref "S4") (pin "1") (pinfunction "O_1") (pintype "passive"))
    )
    (net (code "113") (name "unconnected-(U1-IOB_26-Pad26)") (class "Default")
      (node (ref "U1") (pin "26") (pinfunction "IOB_26_26") (pintype "bidirectional"))
    )
    (net (code "114") (name "unconnected-(U1-IOB_27-Pad27)") (class "Default")
      (node (ref "U1") (pin "27") (pinfunction "IOB_27_27") (pintype "bidirectional"))
    )
    (net (code "115") (name "unconnected-(U1-IOB_28-Pad28)") (class "Default")
      (node (ref "U1") (pin "28") (pinfunction "IOB_28_28") (pintype "bidirectional"))
    )
    (net (code "116") (name "unconnected-(U1-IOB_29-Pad29)") (class "Default")
      (node (ref "U1") (pin "29") (pinfunction "IOB_29_29") (pintype "bidirectional"))
    )
    (net (code "117") (name "unconnected-(U1-IOB_34-Pad36)") (class "Default")
      (node (ref "U1") (pin "36") (pinfunction "IOB_34_36") (pintype "bidirectional"))
    )
    (net (code "118") (name "unconnected-(U1-IOL_1A-Pad1)") (class "Default")
      (node (ref "U1") (pin "1") (pinfunction "IOL_1A_1") (pintype "bidirectional"))
    )
    (net (code "119") (name "unconnected-(U1-IOL_1B-Pad2)") (class "Default")
      (node (ref "U1") (pin "2") (pinfunction "IOL_1B_2") (pintype "bidirectional"))
    )
    (net (code "120") (name "unconnected-(U1-IOL_2A-Pad3)") (class "Default")
      (node (ref "U1") (pin "3") (pinfunction "IOL_2A_3") (pintype "bidirectional"))
    )
    (net (code "121") (name "unconnected-(U1-IOL_2B-Pad4)") (class "Default")
      (node (ref "U1") (pin "4") (pinfunction "IOL_2B_4") (pintype "bidirectional"))
    )
    (net (code "122") (name "unconnected-(U1-IOL_3A-Pad7)") (class "Default")
      (node (ref "U1") (pin "7") (pinfunction "IOL_3A_7") (pintype "bidirectional"))
    )
    (net (code "123") (name "unconnected-(U1-IOL_7B-Pad16)") (class "Default")
      (node (ref "U1") (pin "16") (pinfunction "IOL_7B_16") (pintype "bidirectional"))
    )
    (net (code "124") (name "unconnected-(U1-IOL_12A-Pad24)") (class "Default")
      (node (ref "U1") (pin "24") (pinfunction "IOL_12A_24") (pintype "bidirectional"))
    )
    (net (code "125") (name "unconnected-(U1-IOL_12B-Pad25)") (class "Default")
      (node (ref "U1") (pin "25") (pinfunction "IOL_12B_25") (pintype "bidirectional"))
    )
    (net (code "126") (name "unconnected-(U1-IOR_59-Pad60)") (class "Default")
      (node (ref "U1") (pin "60") (pinfunction "IOR_59_60") (pintype "bidirectional"))
    )
    (net (code "127") (name "unconnected-(U1-IOR_65-Pad66)") (class "Default")
      (node (ref "U1") (pin "66") (pinfunction "IOR_65_66") (pintype "bidirectional"))
    )
    (net (code "128") (name "unconnected-(U1-IOR_67-Pad68)") (class "Default")
      (node (ref "U1") (pin "68") (pinfunction "IOR_67_68") (pintype "bidirectional"))
    )
    (net (code "129") (name "unconnected-(U1-IOR_68-Pad69)") (class "Default")
      (node (ref "U1") (pin "69") (pinfunction "IOR_68_69") (pintype "bidirectional"))
    )
    (net (code "130") (name "unconnected-(U1-IOR_69-Pad71)") (class "Default")
      (node (ref "U1") (pin "71") (pinfunction "IOR_69_71") (pintype "bidirectional"))
    )
    (net (code "131") (name "unconnected-(U1-IOR_70-Pad72)") (class "Default")
      (node (ref "U1") (pin "72") (pinfunction "IOR_70_72") (pintype "bidirectional"))
    )
    (net (code "132") (name "unconnected-(U1-IOT_82-Pad87)") (class "Default")
      (node (ref "U1") (pin "87") (pinfunction "IOT_82_87") (pintype "bidirectional"))
    )
    (net (code "133") (name "unconnected-(U1-IOT_86-Pad91)") (class "Default")
      (node (ref "U1") (pin "91") (pinfunction "IOT_86_91") (pintype "bidirectional"))
    )
    (net (code "134") (name "unconnected-(U1-IOT_87-Pad93)") (class "Default")
      (node (ref "U1") (pin "93") (pinfunction "IOT_87_93") (pintype "bidirectional"))
    )
    (net (code "135") (name "unconnected-(U1-IOT_88-Pad94)") (class "Default")
      (node (ref "U1") (pin "94") (pinfunction "IOT_88_94") (pintype "bidirectional"))
    )
    (net (code "136") (name "unconnected-(U1-IOT_89-Pad95)") (class "Default")
      (node (ref "U1") (pin "95") (pinfunction "IOT_89_95") (pintype "bidirectional"))
    )
    (net (code "137") (name "unconnected-(U1-IOT_90-Pad96)") (class "Default")
      (node (ref "U1") (pin "96") (pinfunction "IOT_90_96") (pintype "bidirectional"))
    )
    (net (code "138") (name "unconnected-(U1-IOT_91-Pad97)") (class "Default")
      (node (ref "U1") (pin "97") (pinfunction "IOT_91_97") (pintype "bidirectional"))
    )
    (net (code "139") (name "unconnected-(U1-IOT_93-Pad99)") (class "Default")
      (node (ref "U1") (pin "99") (pinfunction "IOT_93_99") (pintype "bidirectional"))
    )
    (net (code "140") (name "unconnected-(U1-IOT_95-Pad100)") (class "Default")
      (node (ref "U1") (pin "100") (pinfunction "IOT_95_100") (pintype "bidirectional"))
    )
    (net (code "141") (name "unconnected-(U2-CTS-Pad11)") (class "Default")
      (node (ref "U2") (pin "11") (pinfunction "CTS_11") (pintype "input"))
    )
    (net (code "142") (name "unconnected-(U2-DCD-Pad10)") (class "Default")
      (node (ref "U2") (pin "10") (pinfunction "DCD_10") (pintype "input"))
    )
    (net (code "143") (name "unconnected-(U2-DNU-Pad26)") (class "Default")
      (node (ref "U2") (pin "26") (pinfunction "DNU_26") (pintype "input"))
    )
    (net (code "144") (name "unconnected-(U2-DSR-Pad9)") (class "Default")
      (node (ref "U2") (pin "9") (pinfunction "DSR_9") (pintype "input"))
    )
    (net (code "145") (name "unconnected-(U2-GPIO5-Pad8)") (class "Default")
      (node (ref "U2") (pin "8") (pinfunction "GPIO5_8") (pintype "input"))
    )
    (net (code "146") (name "unconnected-(U2-NC0-Pad24)") (class "Default")
      (node (ref "U2") (pin "24") (pinfunction "NC0_24") (pintype "input"))
    )
    (net (code "147") (name "unconnected-(U2-OSCI-Pad27)") (class "Default")
      (node (ref "U2") (pin "27") (pinfunction "OSCI_27") (pintype "input"))
    )
    (net (code "148") (name "unconnected-(U2-OSCO-Pad28)") (class "Default")
      (node (ref "U2") (pin "28") (pinfunction "OSCO_28") (pintype "output"))
    )
    (net (code "149") (name "unconnected-(U2-PWREN-Pad14)") (class "Default")
      (node (ref "U2") (pin "14") (pinfunction "PWREN_14") (pintype "input"))
    )
    (net (code "150") (name "unconnected-(U2-RI-Pad6)") (class "Default")
      (node (ref "U2") (pin "6") (pinfunction "RI_6") (pintype "input"))
    )
    (net (code "151") (name "unconnected-(U2-RTS-Pad3)") (class "Default")
      (node (ref "U2") (pin "3") (pinfunction "RTS_3") (pintype "output"))
    )
    (net (code "152") (name "unconnected-(U2-RXLED-Pad22)") (class "Default")
      (node (ref "U2") (pin "22") (pinfunction "RXLED_22") (pintype "input"))
    )
    (net (code "153") (name "unconnected-(U2-SLEEP-Pad12)") (class "Default")
      (node (ref "U2") (pin "12") (pinfunction "SLEEP_12") (pintype "input"))
    )
    (net (code "154") (name "unconnected-(U2-TXDEN-Pad13)") (class "Default")
      (node (ref "U2") (pin "13") (pinfunction "TXDEN_13") (pintype "input"))
    )
    (net (code "155") (name "unconnected-(U2-TXLED-Pad23)") (class "Default")
      (node (ref "U2") (pin "23") (pinfunction "TXLED_23") (pintype "input"))
    )
    (net (code "156") (name "unconnected-(U4-ADC7-Pad22)") (class "Default")
      (node (ref "U4") (pin "22") (pinfunction "ADC7_22") (pintype "bidirectional"))
    )
    (net (code "157") (name "unconnected-(U4-PD2(INT0)-Pad32)") (class "Default")
      (node (ref "U4") (pin "32") (pinfunction "PD2(INT0)_32") (pintype "bidirectional"))
    )
    (net (code "158") (name "unconnected-(U4-PD3(INT1)-Pad1)") (class "Default")
      (node (ref "U4") (pin "1") (pinfunction "PD3(INT1)_1") (pintype "bidirectional"))
    )
    (net (code "159") (name "unconnected-(U5-NC{slash}GND-Pad3)") (class "Default")
      (node (ref "U5") (pin "3") (pinfunction "NC/GND_3") (pintype "no_connect"))
    )
    (net (code "160") (name "unconnected-(U5-NC{slash}GND_2-Pad2)") (class "Default")
      (node (ref "U5") (pin "2") (pinfunction "NC/GND_2_2") (pintype "no_connect"))
    )
  )
)
